# EEPROM_DIP_Breakout_WP_Pin_Board.net
KiCad netlist of a schematic drawn in EAGLE
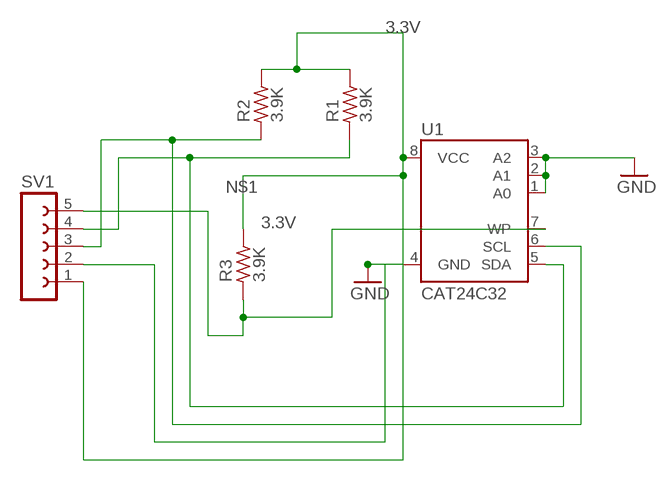
[diagram p0: schematic, sheet 1]

(export (version "E")
  (design (tool "Eeschema 10.0.6"))
  (components
    (comp (ref "R1")
      (value "3.9K")
      (footprint "eagle-import:0204_7")
      (libsource (lib "eagle-import") (part "R_X0204/7"))
    )
    (comp (ref "R2")
      (value "3.9K")
      (footprint "eagle-import:0204_7")
      (libsource (lib "eagle-import") (part "R_X0204/7"))
    )
    (comp (ref "R3")
      (value "3.9K")
      (footprint "eagle-import:0204_7")
      (libsource (lib "eagle-import") (part "R_X0204/7"))
    )
    (comp (ref "SV1")
      (value "FE05-1")
      (footprint "eagle-import:FE05-1")
      (libsource (lib "eagle-import") (part "FE05-1"))
    )
    (comp (ref "U1")
      (value "CAT24C32")
      (footprint "eagle-import:DIL08")
      (fields (field (name "MPN") "AT24C1024BW-SH-B"))
      (libsource (lib "eagle-import") (part "AT24CP"))
    )
  )
  (nets
    (net (code "1") (name "/3.3V") (class "Default")
      (node (ref "R1") (pin "2") (pinfunction "2_2") (pintype "passive"))
      (node (ref "R2") (pin "2") (pinfunction "2_2") (pintype "passive"))
      (node (ref "R3") (pin "2") (pinfunction "2_2") (pintype "passive"))
      (node (ref "SV1") (pin "1") (pinfunction "1_1") (pintype "passive"))
      (node (ref "U1") (pin "8") (pinfunction "VCC_8") (pintype "power_in"))
    )
    (net (code "2") (name "/N$1") (class "Default")
      (node (ref "R1") (pin "1") (pinfunction "1_1") (pintype "passive"))
      (node (ref "SV1") (pin "4") (pinfunction "4_4") (pintype "passive"))
      (node (ref "U1") (pin "5") (pinfunction "SDA_5") (pintype "bidirectional"))
    )
    (net (code "3") (name "GND") (class "Default")
      (node (ref "SV1") (pin "2") (pinfunction "2_2") (pintype "passive"))
      (node (ref "U1") (pin "1") (pinfunction "A0_1") (pintype "input"))
      (node (ref "U1") (pin "2") (pinfunction "A1_2") (pintype "input"))
      (node (ref "U1") (pin "3") (pinfunction "A2_3") (pintype "input"))
      (node (ref "U1") (pin "4") (pinfunction "GND_4") (pintype "power_in"))
    )
    (net (code "4") (name "Net-(U1-SCL)") (class "Default")
      (node (ref "R2") (pin "1") (pinfunction "1_1") (pintype "passive"))
      (node (ref "SV1") (pin "3") (pinfunction "3_3") (pintype "passive"))
      (node (ref "U1") (pin "6") (pinfunction "SCL_6") (pintype "bidirectional"))
    )
    (net (code "5") (name "Net-(U1-WP)") (class "Default")
      (node (ref "R3") (pin "1") (pinfunction "1_1") (pintype "passive"))
      (node (ref "SV1") (pin "5") (pinfunction "5_5") (pintype "passive"))
      (node (ref "U1") (pin "7") (pinfunction "WP_7") (pintype "input"))
    )
  )
)
